# eeZeeProp.net
KiCad netlist of a schematic drawn in EAGLE
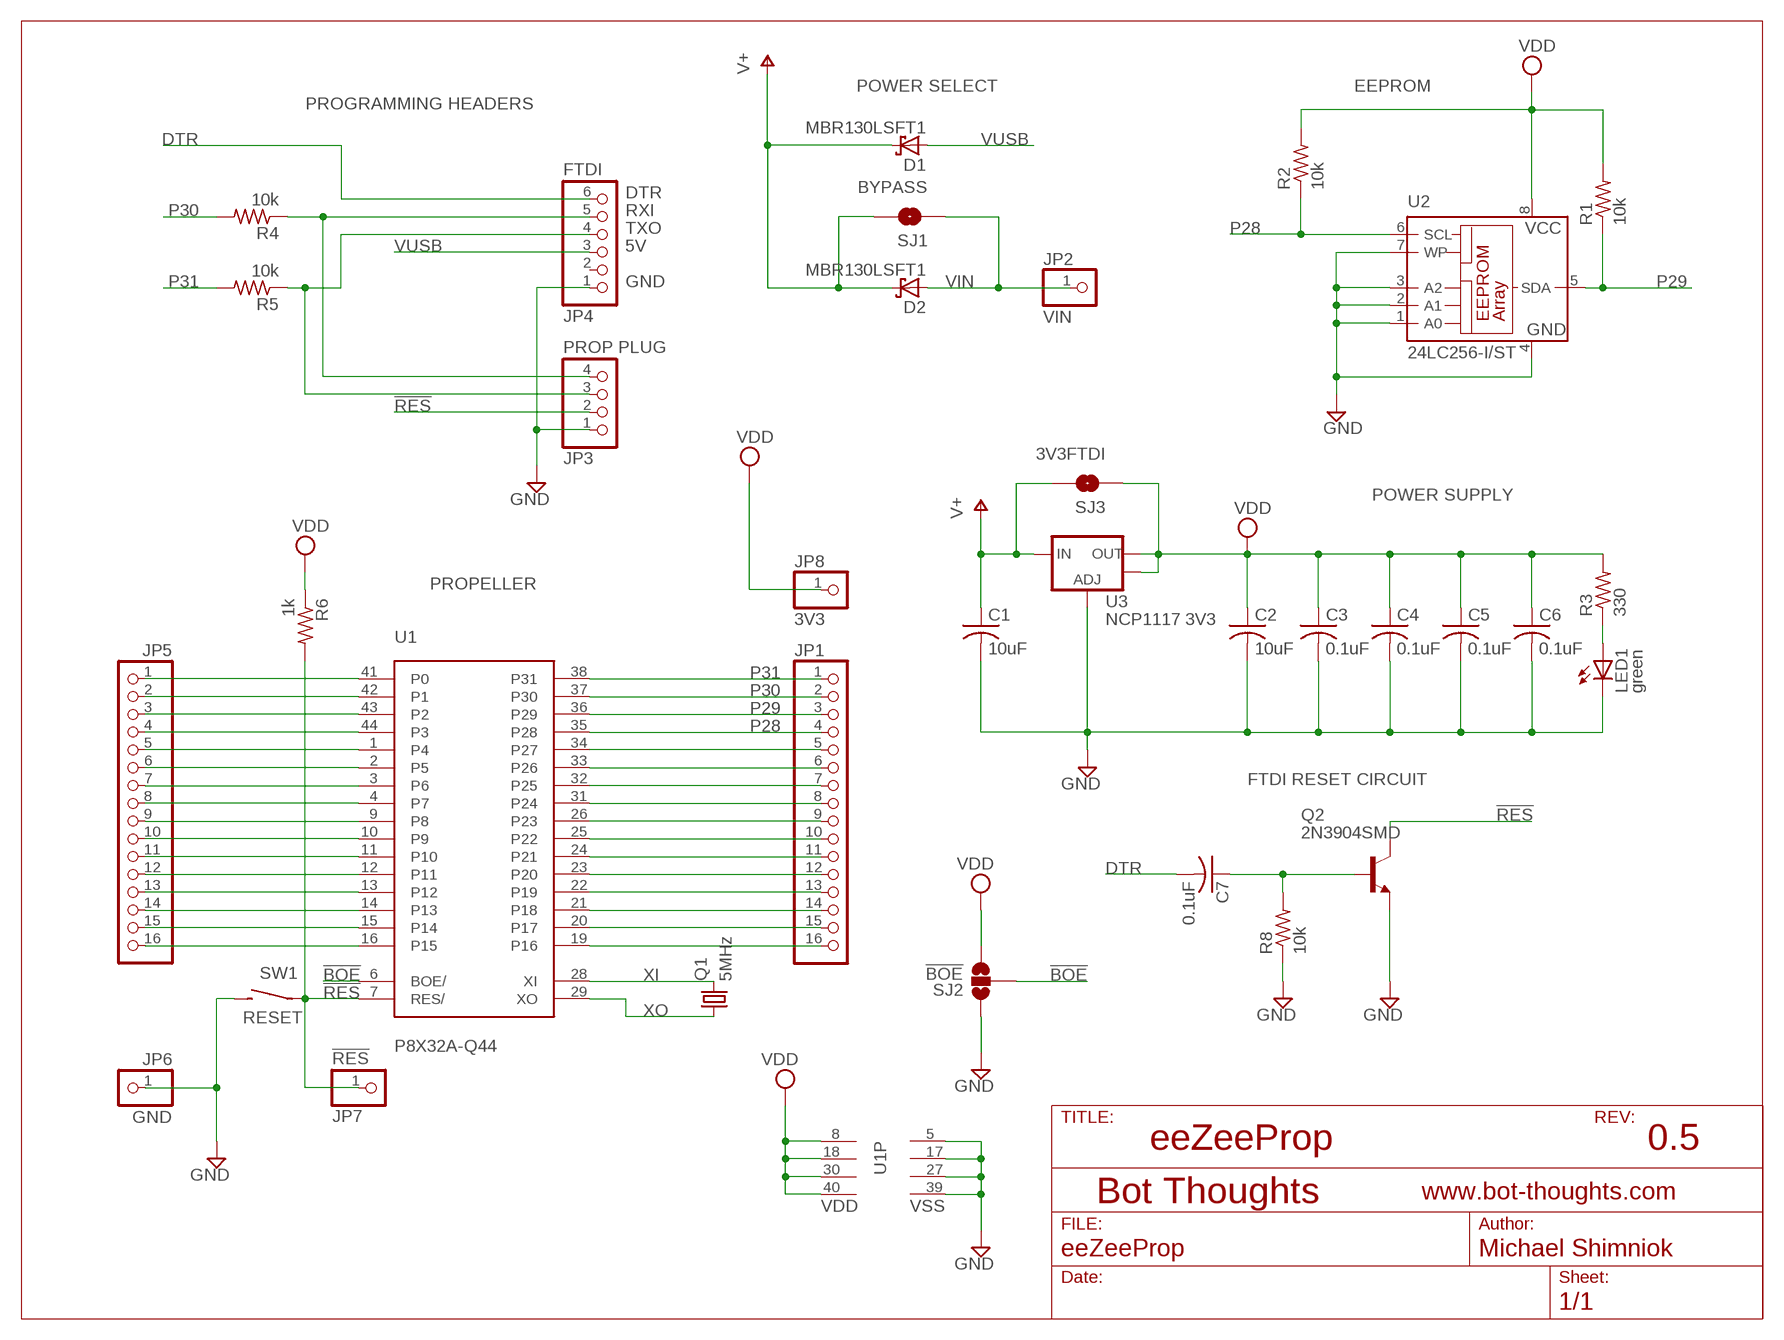
[diagram p0: schematic, sheet 1]

(export (version "E")
  (design (tool "Eeschema 10.0.6"))
  (components
    (comp (ref "C1")
      (value "10uF")
      (footprint "eagle-import:C1206")
      (fields (field (name "PARTNO") "T491A106M006AT"))
      (libsource (lib "eagle-import") (part "C-USC1206"))
    )
    (comp (ref "C2")
      (value "10uF")
      (footprint "eagle-import:C1206")
      (fields (field (name "PARTNO") "T491A106M006AT"))
      (libsource (lib "eagle-import") (part "C-USC1206"))
    )
    (comp (ref "C3")
      (value "0.1uF")
      (footprint "eagle-import:C0603")
      (fields (field (name "PARTNO") "0603YC104KAT2A"))
      (libsource (lib "eagle-import") (part "C-USC0603"))
    )
    (comp (ref "C4")
      (value "0.1uF")
      (footprint "eagle-import:C0603")
      (fields (field (name "PARTNO") "0603YC104KAT2A"))
      (libsource (lib "eagle-import") (part "C-USC0603"))
    )
    (comp (ref "C5")
      (value "0.1uF")
      (footprint "eagle-import:C0603")
      (fields (field (name "PARTNO") "0603YC104KAT2A"))
      (libsource (lib "eagle-import") (part "C-USC0603"))
    )
    (comp (ref "C6")
      (value "0.1uF")
      (footprint "eagle-import:C0603")
      (fields (field (name "PARTNO") "0603YC104KAT2A"))
      (libsource (lib "eagle-import") (part "C-USC0603"))
    )
    (comp (ref "C7")
      (value "0.1uF")
      (footprint "eagle-import:C0603")
      (fields (field (name "PARTNO") "0603YC104KAT2A"))
      (libsource (lib "eagle-import") (part "C-USC0603"))
    )
    (comp (ref "D1")
      (value "MBR130LSFT1")
      (footprint "eagle-import:SOD123FL")
      (fields (field (name "PARTNO") "MBR130LSFT1G"))
      (libsource (lib "eagle-import") (part "SCHOTTKY-DIODE-MBR130LSFT1"))
    )
    (comp (ref "D2")
      (value "MBR130LSFT1")
      (footprint "eagle-import:SOD123FL")
      (fields (field (name "PARTNO") "MBR130LSFT1G"))
      (libsource (lib "eagle-import") (part "SCHOTTKY-DIODE-MBR130LSFT1"))
    )
    (comp (ref "JP1")
      (value "PINHD-1X16_2.54-S")
      (footprint "eagle-import:1X16-S")
      (libsource (lib "eagle-import") (part "PINHD-1X16_2.54-S"))
    )
    (comp (ref "JP2")
      (value "VIN")
      (footprint "eagle-import:1X01")
      (libsource (lib "eagle-import") (part "PINHD-1X01_2.54"))
    )
    (comp (ref "JP3")
      (value "PROP PLUG")
      (footprint "eagle-import:1X04-S")
      (libsource (lib "eagle-import") (part "PINHD-1X04_2.54-S"))
    )
    (comp (ref "JP4")
      (value "FTDI")
      (footprint "eagle-import:1X06-S")
      (fields (field (name "PARTNO") "2211S-06G"))
      (libsource (lib "eagle-import") (part "PINHD-1X06_2.54-S"))
    )
    (comp (ref "JP5")
      (value "PINHD-1X16_2.54-S")
      (footprint "eagle-import:1X16-S")
      (libsource (lib "eagle-import") (part "PINHD-1X16_2.54-S"))
    )
    (comp (ref "JP6")
      (value "GND")
      (footprint "eagle-import:1X01")
      (libsource (lib "eagle-import") (part "PINHD-1X01_2.54"))
    )
    (comp (ref "JP7")
      (value "!RES")
      (footprint "eagle-import:1X01")
      (libsource (lib "eagle-import") (part "PINHD-1X01_2.54"))
    )
    (comp (ref "JP8")
      (value "3V3")
      (footprint "eagle-import:1X01")
      (libsource (lib "eagle-import") (part "PINHD-1X01_2.54"))
    )
    (comp (ref "LED1")
      (value "green")
      (footprint "eagle-import:CHIPLED_1206")
      (fields (field (name "PARTNO") "LG N971-KN-1"))
      (libsource (lib "eagle-import") (part "LEDCHIPLED_1206"))
    )
    (comp (ref "Q1")
      (value "5MHz")
      (footprint "eagle-import:HC49U-V")
      (fields (field (name "OC_FARNELL") "1666969") (field (name "PARTNO") "HC49US-5.000MABJ-UB"))
      (libsource (lib "eagle-import") (part "CRYSTALHC49U-V"))
    )
    (comp (ref "Q2")
      (value "2N3904SMD")
      (footprint "eagle-import:SOT-23")
      (fields (field (name "PARTNO") "MMBT3904LT3G"))
      (libsource (lib "eagle-import") (part "2N3904SMD"))
    )
    (comp (ref "R1")
      (value "10k")
      (footprint "eagle-import:R0603")
      (fields (field (name "PARTNO") "ERJ-3GEYJ103V"))
      (libsource (lib "eagle-import") (part "R-US_R0603"))
    )
    (comp (ref "R2")
      (value "10k")
      (footprint "eagle-import:R0603")
      (fields (field (name "PARTNO") "ERJ-3GEYJ103V"))
      (libsource (lib "eagle-import") (part "R-US_R0603"))
    )
    (comp (ref "R3")
      (value "330")
      (footprint "eagle-import:R0603")
      (fields (field (name "PARTNO") "ERJ-3GEYJ331V"))
      (libsource (lib "eagle-import") (part "R-US_R0603"))
    )
    (comp (ref "R4")
      (value "10k")
      (footprint "eagle-import:R0603")
      (fields (field (name "PARTNO") "RC0603JR-071KL"))
      (libsource (lib "eagle-import") (part "R-US_R0603"))
    )
    (comp (ref "R5")
      (value "10k")
      (footprint "eagle-import:R0603")
      (fields (field (name "PARTNO") "RC0603JR-071KL"))
      (libsource (lib "eagle-import") (part "R-US_R0603"))
    )
    (comp (ref "R6")
      (value "1k")
      (footprint "eagle-import:R0603")
      (fields (field (name "PARTNO") "RC0603JR-071KL"))
      (libsource (lib "eagle-import") (part "R-US_R0603"))
    )
    (comp (ref "R8")
      (value "10k")
      (footprint "eagle-import:R0603")
      (fields (field (name "PARTNO") "ERJ-3GEYJ103V"))
      (libsource (lib "eagle-import") (part "R-US_R0603"))
    )
    (comp (ref "SJ1")
      (value "BYPASS")
      (footprint "eagle-import:SJ_2S-NO")
      (libsource (lib "eagle-import") (part "SOLDERJUMPERNO"))
    )
    (comp (ref "SJ2")
      (value "!BOE")
      (footprint "eagle-import:SJ_3")
      (libsource (lib "eagle-import") (part "SOLDERJUMPER_2WAYS"))
    )
    (comp (ref "SJ3")
      (value "3V3FTDI")
      (footprint "eagle-import:SJ_2S-NO")
      (libsource (lib "eagle-import") (part "SOLDERJUMPERNO"))
    )
    (comp (ref "SW1")
      (value "RESET")
      (footprint "eagle-import:6MMTACTILE_RECT")
      (fields (field (name "PARTNO") "MJTP1243"))
      (libsource (lib "eagle-import") (part "SPST_TAC_RECT1"))
    )
    (comp (ref "U1")
      (value "P8X32A-Q44")
      (footprint "eagle-import:P8X32A-Q44")
      (fields (field (name "PARTNO") "P8X32A-Q44"))
      (libsource (lib "eagle-import") (part "P8X32A-Q44"))
    )
    (comp (ref "U2")
      (value "24LC256-I/ST")
      (footprint "eagle-import:SO-08")
      (fields
        (field (name "MF") "MICROCHIP")
        (field (name "MPN") "24LC128-I/SNG")
        (field (name "MF_1") "OnSemi")
        (field (name "MPN_1") "CAT24C256WI-GT3")
        (field (name "PARTNO") "CAT24C256WI-GT3")
      )
      (libsource (lib "eagle-import") (part "24SNLC128"))
    )
    (comp (ref "U3")
      (value "NCP1117 3V3")
      (footprint "eagle-import:SOT223")
      (fields (field (name "PARTNO") "NCP1117ST33T3G"))
      (libsource (lib "eagle-import") (part "V_REG_LM1117SOT223"))
    )
  )
  (nets
    (net (code "1") (name "/DTR") (class "Default")
      (node (ref "C7") (pin "2") (pinfunction "2_2") (pintype "passive"))
      (node (ref "JP4") (pin "6") (pinfunction "6_6") (pintype "passive"))
    )
    (net (code "2") (name "/P28") (class "Default")
      (node (ref "JP1") (pin "4") (pinfunction "4_4") (pintype "passive"))
      (node (ref "R2") (pin "1") (pinfunction "1_1") (pintype "passive"))
      (node (ref "U1") (pin "35") (pinfunction "P28_35") (pintype "bidirectional"))
      (node (ref "U2") (pin "6") (pinfunction "SCL_6") (pintype "input"))
    )
    (net (code "3") (name "/P29") (class "Default")
      (node (ref "JP1") (pin "3") (pinfunction "3_3") (pintype "passive"))
      (node (ref "R1") (pin "1") (pinfunction "1_1") (pintype "passive"))
      (node (ref "U1") (pin "36") (pinfunction "P29_36") (pintype "bidirectional"))
      (node (ref "U2") (pin "5") (pinfunction "SDA_5") (pintype "bidirectional"))
    )
    (net (code "4") (name "/P30") (class "Default")
      (node (ref "JP1") (pin "2") (pinfunction "2_2") (pintype "passive"))
      (node (ref "R4") (pin "2") (pinfunction "2_2") (pintype "passive"))
      (node (ref "U1") (pin "37") (pinfunction "P30_37") (pintype "bidirectional"))
    )
    (net (code "5") (name "/P31") (class "Default")
      (node (ref "JP1") (pin "1") (pinfunction "1_1") (pintype "passive"))
      (node (ref "R5") (pin "2") (pinfunction "2_2") (pintype "passive"))
      (node (ref "U1") (pin "38") (pinfunction "P31_38") (pintype "bidirectional"))
    )
    (net (code "6") (name "/VIN") (class "Default")
      (node (ref "D2") (pin "A") (pinfunction "A_A") (pintype "passive"))
      (node (ref "JP2") (pin "1") (pinfunction "1_1") (pintype "passive"))
      (node (ref "SJ1") (pin "1") (pinfunction "1_1") (pintype "passive"))
    )
    (net (code "7") (name "/VUSB") (class "Default")
      (node (ref "D1") (pin "A") (pinfunction "A_A") (pintype "passive"))
      (node (ref "JP4") (pin "3") (pinfunction "3_3") (pintype "passive"))
    )
    (net (code "8") (name "/XI") (class "Default")
      (node (ref "Q1") (pin "2") (pinfunction "2_2") (pintype "passive"))
      (node (ref "U1") (pin "28") (pinfunction "XI_28") (pintype "input"))
    )
    (net (code "9") (name "/XO") (class "Default")
      (node (ref "Q1") (pin "1") (pinfunction "1_1") (pintype "passive"))
      (node (ref "U1") (pin "29") (pinfunction "XO_29") (pintype "output"))
    )
    (net (code "10") (name "/~{BOE}") (class "Default")
      (node (ref "SJ2") (pin "2") (pinfunction "2_2") (pintype "passive"))
      (node (ref "U1") (pin "6") (pinfunction "BOE/_6") (pintype "input"))
    )
    (net (code "11") (name "/~{RES}") (class "Default")
      (node (ref "JP3") (pin "2") (pinfunction "2_2") (pintype "passive"))
      (node (ref "JP7") (pin "1") (pinfunction "1_1") (pintype "passive"))
      (node (ref "Q2") (pin "1") (pinfunction "C_1") (pintype "passive"))
      (node (ref "R6") (pin "2") (pinfunction "2_2") (pintype "passive"))
      (node (ref "SW1") (pin "P$1") (pinfunction "P_P$1") (pintype "passive"))
      (node (ref "U1") (pin "7") (pinfunction "RES/_7") (pintype "bidirectional"))
    )
    (net (code "12") (name "GND") (class "Default")
      (node (ref "C1") (pin "2") (pinfunction "2_2") (pintype "passive"))
      (node (ref "C2") (pin "2") (pinfunction "2_2") (pintype "passive"))
      (node (ref "C3") (pin "2") (pinfunction "2_2") (pintype "passive"))
      (node (ref "C4") (pin "2") (pinfunction "2_2") (pintype "passive"))
      (node (ref "C5") (pin "2") (pinfunction "2_2") (pintype "passive"))
      (node (ref "C6") (pin "2") (pinfunction "2_2") (pintype "passive"))
      (node (ref "JP3") (pin "1") (pinfunction "1_1") (pintype "passive"))
      (node (ref "JP4") (pin "1") (pinfunction "1_1") (pintype "passive"))
      (node (ref "JP6") (pin "1") (pinfunction "1_1") (pintype "passive"))
      (node (ref "LED1") (pin "C") (pinfunction "C_C") (pintype "passive"))
      (node (ref "Q2") (pin "2") (pinfunction "E_2") (pintype "passive"))
      (node (ref "R8") (pin "1") (pinfunction "1_1") (pintype "passive"))
      (node (ref "SJ2") (pin "1") (pinfunction "1_1") (pintype "passive"))
      (node (ref "SW1") (pin "P$2") (pinfunction "S_P$2") (pintype "passive"))
      (node (ref "U1") (pin "17") (pinfunction "VSS_17") (pintype "power_in"))
      (node (ref "U1") (pin "27") (pinfunction "VSS_27") (pintype "power_in"))
      (node (ref "U1") (pin "39") (pinfunction "VSS_39") (pintype "power_in"))
      (node (ref "U1") (pin "5") (pinfunction "VSS_5") (pintype "power_in"))
      (node (ref "U2") (pin "1") (pinfunction "A0_1") (pintype "input"))
      (node (ref "U2") (pin "2") (pinfunction "A1_2") (pintype "input"))
      (node (ref "U2") (pin "3") (pinfunction "A2_3") (pintype "input"))
      (node (ref "U2") (pin "4") (pinfunction "GND_4") (pintype "power_in"))
      (node (ref "U2") (pin "7") (pinfunction "WP_7") (pintype "input"))
      (node (ref "U3") (pin "1") (pinfunction "ADJ_1") (pintype "input"))
    )
    (net (code "13") (name "Net-(JP3-Pad3)") (class "Default")
      (node (ref "JP3") (pin "3") (pinfunction "3_3") (pintype "passive"))
      (node (ref "JP4") (pin "4") (pinfunction "4_4") (pintype "passive"))
      (node (ref "R5") (pin "1") (pinfunction "1_1") (pintype "passive"))
    )
    (net (code "14") (name "Net-(JP3-Pad4)") (class "Default")
      (node (ref "JP3") (pin "4") (pinfunction "4_4") (pintype "passive"))
      (node (ref "JP4") (pin "5") (pinfunction "5_5") (pintype "passive"))
      (node (ref "R4") (pin "1") (pinfunction "1_1") (pintype "passive"))
    )
    (net (code "15") (name "Net-(LED1-PadA)") (class "Default")
      (node (ref "LED1") (pin "A") (pinfunction "A_A") (pintype "passive"))
      (node (ref "R3") (pin "1") (pinfunction "1_1") (pintype "passive"))
    )
    (net (code "16") (name "Net-(Q2-B)") (class "Default")
      (node (ref "C7") (pin "1") (pinfunction "1_1") (pintype "passive"))
      (node (ref "Q2") (pin "3") (pinfunction "B_3") (pintype "passive"))
      (node (ref "R8") (pin "2") (pinfunction "2_2") (pintype "passive"))
    )
    (net (code "17") (name "Net-(U1B-P0)") (class "Default")
      (node (ref "JP5") (pin "1") (pinfunction "1_1") (pintype "passive"))
      (node (ref "U1") (pin "41") (pinfunction "P0_41") (pintype "bidirectional"))
    )
    (net (code "18") (name "Net-(U1B-P1)") (class "Default")
      (node (ref "JP5") (pin "2") (pinfunction "2_2") (pintype "passive"))
      (node (ref "U1") (pin "42") (pinfunction "P1_42") (pintype "bidirectional"))
    )
    (net (code "19") (name "Net-(U1B-P2)") (class "Default")
      (node (ref "JP5") (pin "3") (pinfunction "3_3") (pintype "passive"))
      (node (ref "U1") (pin "43") (pinfunction "P2_43") (pintype "bidirectional"))
    )
    (net (code "20") (name "Net-(U1B-P3)") (class "Default")
      (node (ref "JP5") (pin "4") (pinfunction "4_4") (pintype "passive"))
      (node (ref "U1") (pin "44") (pinfunction "P3_44") (pintype "bidirectional"))
    )
    (net (code "21") (name "Net-(U1B-P4)") (class "Default")
      (node (ref "JP5") (pin "5") (pinfunction "5_5") (pintype "passive"))
      (node (ref "U1") (pin "1") (pinfunction "P4_1") (pintype "bidirectional"))
    )
    (net (code "22") (name "Net-(U1B-P5)") (class "Default")
      (node (ref "JP5") (pin "6") (pinfunction "6_6") (pintype "passive"))
      (node (ref "U1") (pin "2") (pinfunction "P5_2") (pintype "bidirectional"))
    )
    (net (code "23") (name "Net-(U1B-P6)") (class "Default")
      (node (ref "JP5") (pin "7") (pinfunction "7_7") (pintype "passive"))
      (node (ref "U1") (pin "3") (pinfunction "P6_3") (pintype "bidirectional"))
    )
    (net (code "24") (name "Net-(U1B-P7)") (class "Default")
      (node (ref "JP5") (pin "8") (pinfunction "8_8") (pintype "passive"))
      (node (ref "U1") (pin "4") (pinfunction "P7_4") (pintype "bidirectional"))
    )
    (net (code "25") (name "Net-(U1B-P8)") (class "Default")
      (node (ref "JP5") (pin "9") (pinfunction "9_9") (pintype "passive"))
      (node (ref "U1") (pin "9") (pinfunction "P8_9") (pintype "bidirectional"))
    )
    (net (code "26") (name "Net-(U1B-P9)") (class "Default")
      (node (ref "JP5") (pin "10") (pinfunction "10_10") (pintype "passive"))
      (node (ref "U1") (pin "10") (pinfunction "P9_10") (pintype "bidirectional"))
    )
    (net (code "27") (name "Net-(U1B-P10)") (class "Default")
      (node (ref "JP5") (pin "11") (pinfunction "11_11") (pintype "passive"))
      (node (ref "U1") (pin "11") (pinfunction "P10_11") (pintype "bidirectional"))
    )
    (net (code "28") (name "Net-(U1B-P11)") (class "Default")
      (node (ref "JP5") (pin "12") (pinfunction "12_12") (pintype "passive"))
      (node (ref "U1") (pin "12") (pinfunction "P11_12") (pintype "bidirectional"))
    )
    (net (code "29") (name "Net-(U1B-P12)") (class "Default")
      (node (ref "JP5") (pin "13") (pinfunction "13_13") (pintype "passive"))
      (node (ref "U1") (pin "13") (pinfunction "P12_13") (pintype "bidirectional"))
    )
    (net (code "30") (name "Net-(U1B-P13)") (class "Default")
      (node (ref "JP5") (pin "14") (pinfunction "14_14") (pintype "passive"))
      (node (ref "U1") (pin "14") (pinfunction "P13_14") (pintype "bidirectional"))
    )
    (net (code "31") (name "Net-(U1B-P14)") (class "Default")
      (node (ref "JP5") (pin "15") (pinfunction "15_15") (pintype "passive"))
      (node (ref "U1") (pin "15") (pinfunction "P14_15") (pintype "bidirectional"))
    )
    (net (code "32") (name "Net-(U1B-P15)") (class "Default")
      (node (ref "JP5") (pin "16") (pinfunction "16_16") (pintype "passive"))
      (node (ref "U1") (pin "16") (pinfunction "P15_16") (pintype "bidirectional"))
    )
    (net (code "33") (name "Net-(U1B-P16)") (class "Default")
      (node (ref "JP1") (pin "16") (pinfunction "16_16") (pintype "passive"))
      (node (ref "U1") (pin "19") (pinfunction "P16_19") (pintype "bidirectional"))
    )
    (net (code "34") (name "Net-(U1B-P17)") (class "Default")
      (node (ref "JP1") (pin "15") (pinfunction "15_15") (pintype "passive"))
      (node (ref "U1") (pin "20") (pinfunction "P17_20") (pintype "bidirectional"))
    )
    (net (code "35") (name "Net-(U1B-P18)") (class "Default")
      (node (ref "JP1") (pin "14") (pinfunction "14_14") (pintype "passive"))
      (node (ref "U1") (pin "21") (pinfunction "P18_21") (pintype "bidirectional"))
    )
    (net (code "36") (name "Net-(U1B-P19)") (class "Default")
      (node (ref "JP1") (pin "13") (pinfunction "13_13") (pintype "passive"))
      (node (ref "U1") (pin "22") (pinfunction "P19_22") (pintype "bidirectional"))
    )
    (net (code "37") (name "Net-(U1B-P20)") (class "Default")
      (node (ref "JP1") (pin "12") (pinfunction "12_12") (pintype "passive"))
      (node (ref "U1") (pin "23") (pinfunction "P20_23") (pintype "bidirectional"))
    )
    (net (code "38") (name "Net-(U1B-P21)") (class "Default")
      (node (ref "JP1") (pin "11") (pinfunction "11_11") (pintype "passive"))
      (node (ref "U1") (pin "24") (pinfunction "P21_24") (pintype "bidirectional"))
    )
    (net (code "39") (name "Net-(U1B-P22)") (class "Default")
      (node (ref "JP1") (pin "10") (pinfunction "10_10") (pintype "passive"))
      (node (ref "U1") (pin "25") (pinfunction "P22_25") (pintype "bidirectional"))
    )
    (net (code "40") (name "Net-(U1B-P23)") (class "Default")
      (node (ref "JP1") (pin "9") (pinfunction "9_9") (pintype "passive"))
      (node (ref "U1") (pin "26") (pinfunction "P23_26") (pintype "bidirectional"))
    )
    (net (code "41") (name "Net-(U1B-P24)") (class "Default")
      (node (ref "JP1") (pin "8") (pinfunction "8_8") (pintype "passive"))
      (node (ref "U1") (pin "31") (pinfunction "P24_31") (pintype "bidirectional"))
    )
    (net (code "42") (name "Net-(U1B-P25)") (class "Default")
      (node (ref "JP1") (pin "7") (pinfunction "7_7") (pintype "passive"))
      (node (ref "U1") (pin "32") (pinfunction "P25_32") (pintype "bidirectional"))
    )
    (net (code "43") (name "Net-(U1B-P26)") (class "Default")
      (node (ref "JP1") (pin "6") (pinfunction "6_6") (pintype "passive"))
      (node (ref "U1") (pin "33") (pinfunction "P26_33") (pintype "bidirectional"))
    )
    (net (code "44") (name "Net-(U1B-P27)") (class "Default")
      (node (ref "JP1") (pin "5") (pinfunction "5_5") (pintype "passive"))
      (node (ref "U1") (pin "34") (pinfunction "P27_34") (pintype "bidirectional"))
    )
    (net (code "45") (name "V+") (class "Default")
      (node (ref "C1") (pin "1") (pinfunction "1_1") (pintype "passive"))
      (node (ref "D1") (pin "C") (pinfunction "C_C") (pintype "passive"))
      (node (ref "D2") (pin "C") (pinfunction "C_C") (pintype "passive"))
      (node (ref "SJ1") (pin "2") (pinfunction "2_2") (pintype "passive"))
      (node (ref "SJ3") (pin "2") (pinfunction "2_2") (pintype "passive"))
      (node (ref "U3") (pin "3") (pinfunction "IN_3") (pintype "input"))
    )
    (net (code "46") (name "VDD") (class "Default")
      (node (ref "C2") (pin "1") (pinfunction "1_1") (pintype "passive"))
      (node (ref "C3") (pin "1") (pinfunction "1_1") (pintype "passive"))
      (node (ref "C4") (pin "1") (pinfunction "1_1") (pintype "passive"))
      (node (ref "C5") (pin "1") (pinfunction "1_1") (pintype "passive"))
      (node (ref "C6") (pin "1") (pinfunction "1_1") (pintype "passive"))
      (node (ref "JP8") (pin "1") (pinfunction "1_1") (pintype "passive"))
      (node (ref "R1") (pin "2") (pinfunction "2_2") (pintype "passive"))
      (node (ref "R2") (pin "2") (pinfunction "2_2") (pintype "passive"))
      (node (ref "R3") (pin "2") (pinfunction "2_2") (pintype "passive"))
      (node (ref "R6") (pin "1") (pinfunction "1_1") (pintype "passive"))
      (node (ref "SJ2") (pin "3") (pinfunction "3_3") (pintype "passive"))
      (node (ref "SJ3") (pin "1") (pinfunction "1_1") (pintype "passive"))
      (node (ref "U1") (pin "18") (pinfunction "VDD_18") (pintype "power_in"))
      (node (ref "U1") (pin "30") (pinfunction "VDD_30") (pintype "power_in"))
      (node (ref "U1") (pin "40") (pinfunction "VDD_40") (pintype "power_in"))
      (node (ref "U1") (pin "8") (pinfunction "VDD_8") (pintype "power_in"))
      (node (ref "U2") (pin "8") (pinfunction "VCC_8") (pintype "power_in"))
      (node (ref "U3") (pin "2") (pinfunction "OUT_2") (pintype "output"))
      (node (ref "U3") (pin "4") (pinfunction "OUT_4") (pintype "output"))
    )
    (net (code "47") (name "unconnected-(JP4-Pad2)") (class "Default")
      (node (ref "JP4") (pin "2") (pinfunction "2_2") (pintype "passive"))
    )
  )
)
